# HV-Measurement.net
KiCad netlist of a schematic drawn in Altium Designer
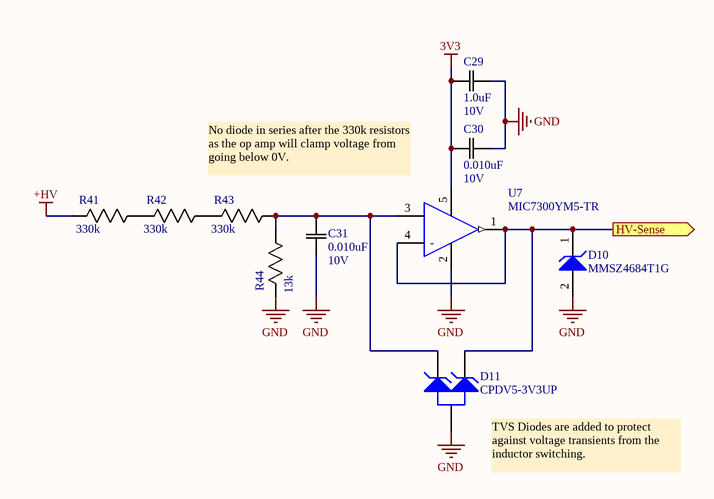
[diagram p0: HV-Measurement.SchDoc]

(export (version "E")
  (design (tool "Eeschema 10.0.6"))
  (components
    (comp (ref "C29")
      (value "1.0uF")
      (footprint "0603")
      (description "CAP CER 1.0UF 10V X5R 0603")
      (fields (field (name "TOLERANCE") "10%") (field (name "RATING") "10V"))
      (libsource (lib "AltiumLibraries") (part "CAP 1.0uF 16V"))
    )
    (comp (ref "C30")
      (value "0.010uF")
      (footprint "0603")
      (description "CAP CER 0.010UF 10V X7R 0603")
      (fields (field (name "TOLERANCE") "10%") (field (name "RATING") "10V"))
      (libsource (lib "AltiumLibraries") (part "CAP 0.010uF 16V"))
    )
    (comp (ref "C31")
      (value "0.010uF")
      (footprint "0603")
      (description "CAP CER 0.010UF 10V X7R 0603")
      (fields (field (name "TOLERANCE") "10%") (field (name "RATING") "10V"))
      (libsource (lib "AltiumLibraries") (part "CAP 0.010uF 16V"))
    )
    (comp (ref "D10")
      (value "MMSZ4684T1G")
      (footprint "ONSC-SOD-123-2-425-04_V")
      (description "Zener Voltage Regulator, 500 mW, 2-Pin SOD-123, Pb-Free, Tape and Reel")
      (fields (field (name "MANUFACTURER") "On Semiconductor"))
      (libsource (lib "Altium Content Vault") (part "ONSC-K1A2-2"))
    )
    (comp (ref "D11")
      (value "CPDV5-3V3UP")
      (footprint "ONSC-SOT-723-3-631AA-01_V")
      (fields (field (name "PARTNUMBER") "ESD7L5.0DT5G") (field (name "MANUFACTURER") "On Semiconductor"))
      (libsource (lib "Altium Content Vault") (part "ONSC-K1K2A3-3"))
    )
    (comp (ref "R41")
      (value "330k")
      (footprint "0805")
      (description "RES SMD 330K OHM 5% 1/8W 0805")
      (fields (field (name "TOLERANCE") "5%"))
      (libsource (lib "") (part "RES 330k 1/8W - 5%_1"))
    )
    (comp (ref "R42")
      (value "330k")
      (footprint "0805")
      (description "CRCW0805330KFKEA")
      (fields (field (name "TOLERANCE") "5%"))
      (libsource (lib "AltiumLibraries") (part "RES 330k 1/8W - 5%"))
    )
    (comp (ref "R43")
      (value "330k")
      (footprint "0805")
      (description "RES SMD 330K OHM 5% 1/8W 0805")
      (fields (field (name "TOLERANCE") "5%"))
      (libsource (lib "AltiumLibraries") (part "RES 330k 1/8W - 5%"))
    )
    (comp (ref "R44")
      (value "13k")
      (footprint "0805")
      (description "RES SMD 13K OHM 5% 1/8W 0805")
      (fields (field (name "TOLERANCE") "5%"))
      (libsource (lib "AltiumLibraries") (part "RES 13k 1/8W"))
    )
    (comp (ref "U7")
      (value "MIC7300YM5-TR")
      (footprint "FP-SOT23-5LD-PL-1-MFG")
      (description "IC OPAMP GP 1 CIRCUIT SOT23-5")
      (fields
        (field (name "OCTOPART") "https://octopart.com/mic7300ym5-tr-microchip-66803593")
        (field (name "MANUFACTURER") "Microchip")
      )
      (libsource (lib "Altium Content Vault") (part "a2fe186d2557ed0e36928d4a518c7fe"))
    )
  )
  (nets
    (net (code "1") (name "+HV") (class "Default")
      (node (ref "R41") (pin "2") (pinfunction "R2_2") (pintype "passive"))
    )
    (net (code "2") (name "/HV-Sense") (class "Default")
      (node (ref "D10") (pin "1") (pinfunction "K_1") (pintype "passive"))
      (node (ref "D11") (pin "2") (pinfunction "K2_2") (pintype "passive"))
      (node (ref "U7") (pin "1") (pinfunction "OUT_1") (pintype "output"))
      (node (ref "U7") (pin "4") (pinfunction "IN-_4") (pintype "passive"))
    )
    (net (code "3") (name "3V3") (class "Default")
      (node (ref "C29") (pin "2") (pinfunction "C2_2") (pintype "passive"))
      (node (ref "C30") (pin "1") (pinfunction "C1_1") (pintype "passive"))
      (node (ref "U7") (pin "5") (pinfunction "V+_5") (pintype "power_in"))
    )
    (net (code "4") (name "GND") (class "Default")
      (node (ref "C29") (pin "1") (pinfunction "C1_1") (pintype "passive"))
      (node (ref "C30") (pin "2") (pinfunction "C2_2") (pintype "passive"))
      (node (ref "C31") (pin "1") (pinfunction "C1_1") (pintype "passive"))
      (node (ref "D10") (pin "2") (pinfunction "A_2") (pintype "passive"))
      (node (ref "D11") (pin "3") (pinfunction "A_3") (pintype "passive"))
      (node (ref "R44") (pin "2") (pinfunction "R2_2") (pintype "passive"))
      (node (ref "U7") (pin "2") (pinfunction "V-_2") (pintype "power_in"))
    )
    (net (code "5") (name "Net-(C31-C2)") (class "Default")
      (node (ref "C31") (pin "2") (pinfunction "C2_2") (pintype "passive"))
      (node (ref "D11") (pin "1") (pinfunction "K1_1") (pintype "passive"))
      (node (ref "R43") (pin "1") (pinfunction "R1_1") (pintype "passive"))
      (node (ref "R44") (pin "1") (pinfunction "R1_1") (pintype "passive"))
      (node (ref "U7") (pin "3") (pinfunction "IN+_3") (pintype "passive"))
    )
    (net (code "6") (name "Net-(R41-R1)") (class "Default")
      (node (ref "R41") (pin "1") (pinfunction "R1_1") (pintype "passive"))
      (node (ref "R42") (pin "2") (pinfunction "R2_2") (pintype "passive"))
    )
    (net (code "7") (name "Net-(R42-R1)") (class "Default")
      (node (ref "R42") (pin "1") (pinfunction "R1_1") (pintype "passive"))
      (node (ref "R43") (pin "2") (pinfunction "R2_2") (pintype "passive"))
    )
  )
)
